# 04_ZYNQ_MISC_INTERFACE.net
KiCad netlist of a schematic drawn in Altium Designer
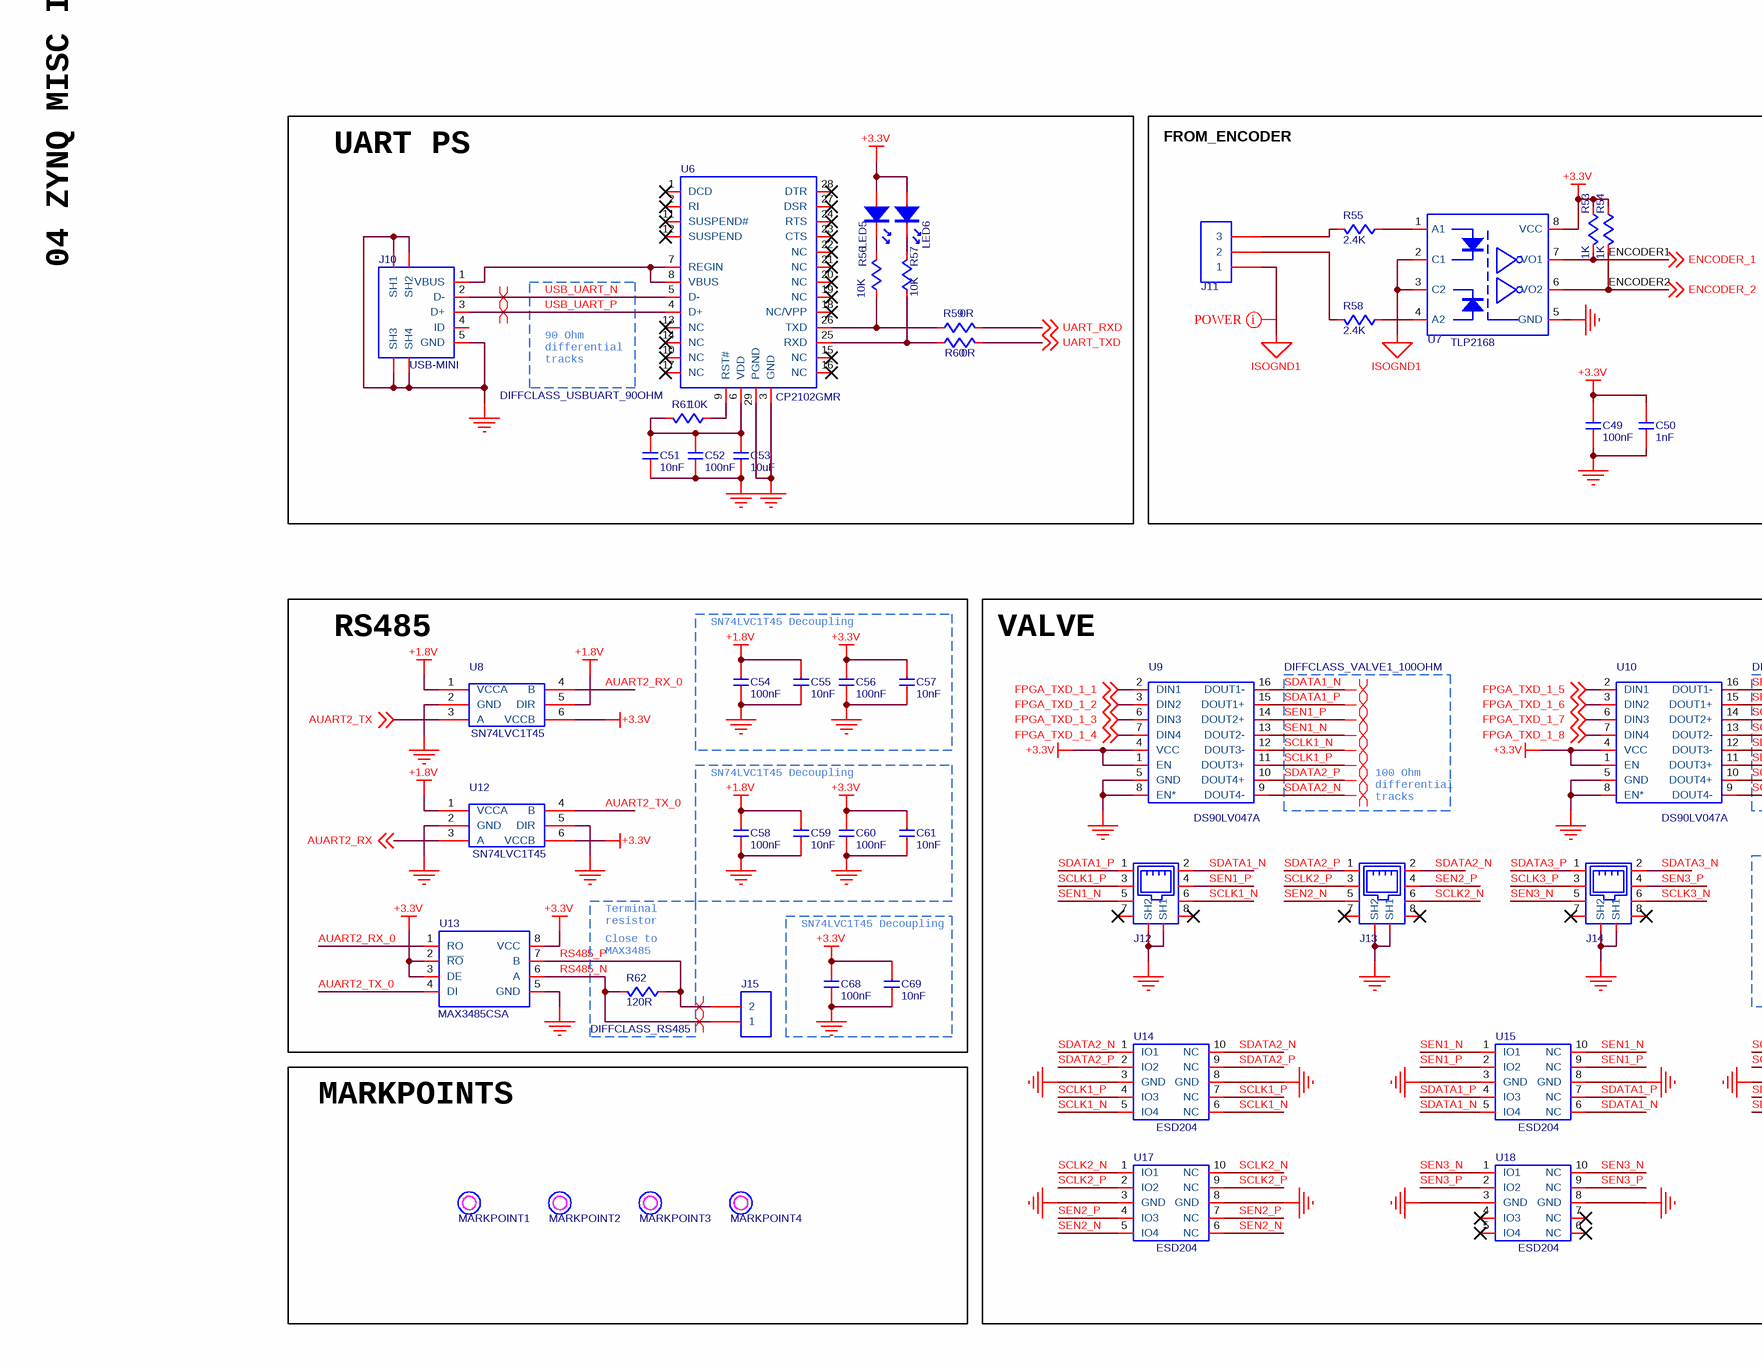
[diagram p0: 04_ZYNQ_MISC_INTERFACE.SchDoc, left]
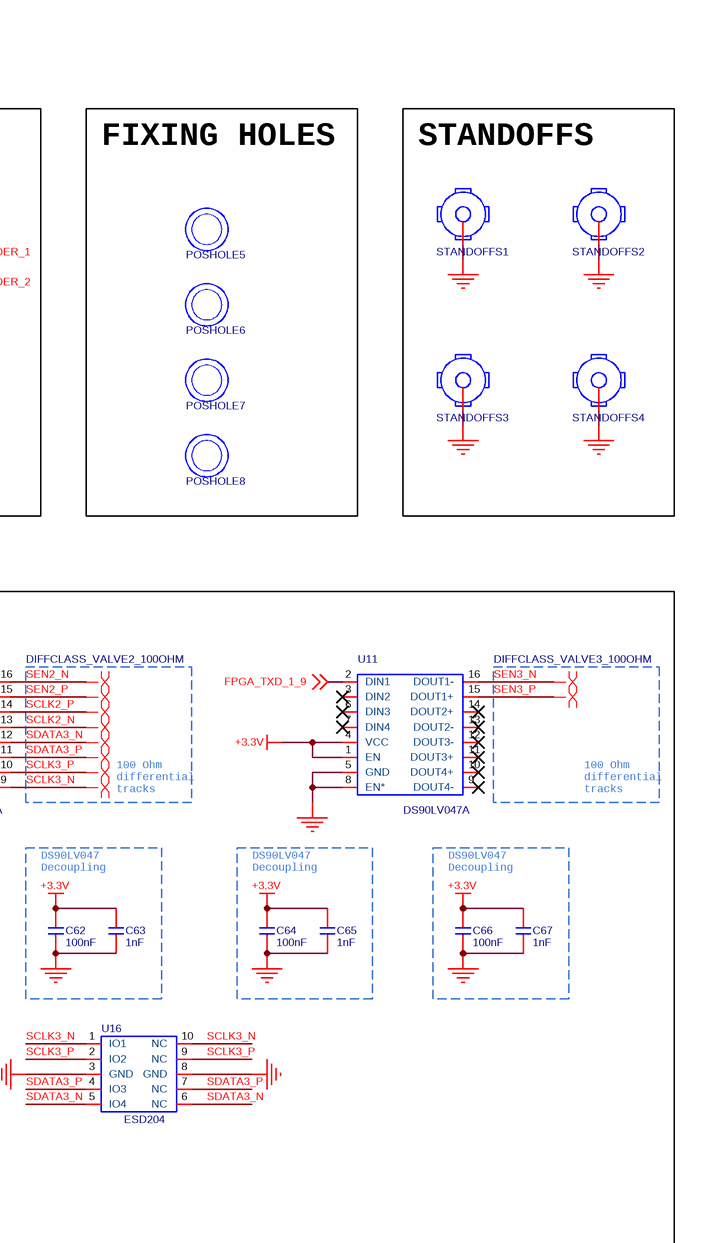
[diagram p1: 04_ZYNQ_MISC_INTERFACE.SchDoc, right]

(export (version "E")
  (design (tool "Eeschema 10.0.6"))
  (components
    (comp (ref "C49")
      (value "100nF")
      (footprint "zynq:C0402")
      (fields (field (name "VOLTAGE") "25V") (field (name "Comment") "C-NOMO"))
      (libsource (lib "mw") (part "C-NOMO"))
    )
    (comp (ref "C50")
      (value "1nF")
      (footprint "zynq:C0402")
      (fields (field (name "VOLTAGE") "25V") (field (name "Comment") "C-NOMO"))
      (libsource (lib "mw") (part "C-NOMO"))
    )
    (comp (ref "C51")
      (value "10nF")
      (footprint "zynq:C0402")
      (fields (field (name "VOLTAGE") "25V") (field (name "Comment") "C-NOMO"))
      (libsource (lib "zynq") (part "C-NOMO"))
    )
    (comp (ref "C52")
      (value "100nF")
      (footprint "zynq:C0402")
      (fields (field (name "VOLTAGE") "25V") (field (name "Comment") "C-NOMO"))
      (libsource (lib "zynq") (part "C-NOMO"))
    )
    (comp (ref "C53")
      (value "10uF")
      (footprint "zynq:C0805")
      (fields (field (name "VOLTAGE") "25V") (field (name "Comment") "C-NOMO"))
      (libsource (lib "zynq") (part "C-NOMO"))
    )
    (comp (ref "C54")
      (value "100nF")
      (footprint "zynq:C0402")
      (fields (field (name "VOLTAGE") "25V") (field (name "Comment") "C-NOMO"))
      (libsource (lib "zynq") (part "C-NOMO"))
    )
    (comp (ref "C55")
      (value "10nF")
      (footprint "zynq:C0402")
      (fields (field (name "VOLTAGE") "25V") (field (name "Comment") "C-NOMO"))
      (libsource (lib "zynq") (part "C-NOMO"))
    )
    (comp (ref "C56")
      (value "100nF")
      (footprint "zynq:C0402")
      (fields (field (name "VOLTAGE") "25V") (field (name "Comment") "C-NOMO"))
      (libsource (lib "zynq") (part "C-NOMO"))
    )
    (comp (ref "C57")
      (value "10nF")
      (footprint "zynq:C0402")
      (fields (field (name "VOLTAGE") "25V") (field (name "Comment") "C-NOMO"))
      (libsource (lib "zynq") (part "C-NOMO"))
    )
    (comp (ref "C58")
      (value "100nF")
      (footprint "zynq:C0402")
      (fields (field (name "VOLTAGE") "25V") (field (name "Comment") "C-NOMO"))
      (libsource (lib "zynq") (part "C-NOMO"))
    )
    (comp (ref "C59")
      (value "10nF")
      (footprint "zynq:C0402")
      (fields (field (name "VOLTAGE") "25V") (field (name "Comment") "C-NOMO"))
      (libsource (lib "zynq") (part "C-NOMO"))
    )
    (comp (ref "C60")
      (value "100nF")
      (footprint "zynq:C0402")
      (fields (field (name "VOLTAGE") "25V") (field (name "Comment") "C-NOMO"))
      (libsource (lib "zynq") (part "C-NOMO"))
    )
    (comp (ref "C61")
      (value "10nF")
      (footprint "zynq:C0402")
      (fields (field (name "VOLTAGE") "25V") (field (name "Comment") "C-NOMO"))
      (libsource (lib "zynq") (part "C-NOMO"))
    )
    (comp (ref "C62")
      (value "100nF")
      (footprint "zynq:C0402")
      (fields (field (name "VOLTAGE") "25V") (field (name "Comment") "C-NOMO"))
      (libsource (lib "zynq") (part "C-NOMO"))
    )
    (comp (ref "C63")
      (value "1nF")
      (footprint "zynq:C0402")
      (fields (field (name "VOLTAGE") "25V") (field (name "Comment") "C-NOMO"))
      (libsource (lib "zynq") (part "C-NOMO"))
    )
    (comp (ref "C64")
      (value "100nF")
      (footprint "zynq:C0402")
      (fields (field (name "VOLTAGE") "25V") (field (name "Comment") "C-NOMO"))
      (libsource (lib "zynq") (part "C-NOMO"))
    )
    (comp (ref "C65")
      (value "1nF")
      (footprint "zynq:C0402")
      (fields (field (name "VOLTAGE") "25V") (field (name "Comment") "C-NOMO"))
      (libsource (lib "zynq") (part "C-NOMO"))
    )
    (comp (ref "C66")
      (value "100nF")
      (footprint "zynq:C0402")
      (fields (field (name "VOLTAGE") "25V") (field (name "Comment") "C-NOMO"))
      (libsource (lib "zynq") (part "C-NOMO"))
    )
    (comp (ref "C67")
      (value "1nF")
      (footprint "zynq:C0402")
      (fields (field (name "VOLTAGE") "25V") (field (name "Comment") "C-NOMO"))
      (libsource (lib "zynq") (part "C-NOMO"))
    )
    (comp (ref "C68")
      (value "100nF")
      (footprint "zynq:C0402")
      (fields (field (name "VOLTAGE") "25V") (field (name "Comment") "C-NOMO"))
      (libsource (lib "zynq") (part "C-NOMO"))
    )
    (comp (ref "C69")
      (value "10nF")
      (footprint "zynq:C0402")
      (fields (field (name "VOLTAGE") "25V") (field (name "Comment") "C-NOMO"))
      (libsource (lib "zynq") (part "C-NOMO"))
    )
    (comp (ref "J10")
      (value "USB-MINI")
      (footprint "zynq:USB-MINI")
      (libsource (lib "zynq") (part "USB-MINI"))
    )
    (comp (ref "J11") (value "HDR1X3") (footprint "zynq:KF301-5.0-3P") (libsource (lib "mw") (part "HDR1X3")))
    (comp (ref "J12") (value "RJ45-UP") (footprint "zynq:RJ45-UP") (libsource (lib "mw") (part "RJ45-UP")))
    (comp (ref "J13") (value "RJ45-UP") (footprint "zynq:RJ45-UP") (libsource (lib "mw") (part "RJ45-UP")))
    (comp (ref "J14") (value "RJ45-UP") (footprint "zynq:RJ45-UP") (libsource (lib "mw") (part "RJ45-UP")))
    (comp (ref "J15")
      (value "HDR1X2")
      (footprint "zynq:KF301-5.0-2P")
      (libsource (lib "zynq") (part "HDR1X2"))
    )
    (comp (ref "LED5") (value "LED") (footprint "zynq:LED0603") (libsource (lib "zynq") (part "LED")))
    (comp (ref "LED6") (value "LED") (footprint "zynq:LED0603") (libsource (lib "zynq") (part "LED")))
    (comp (ref "MARKPOINT1")
      (value "MARKPOINT")
      (footprint "zynq:MARKPOINT-1.0")
      (libsource (lib "zynq") (part "MARKPOINT"))
    )
    (comp (ref "MARKPOINT2")
      (value "MARKPOINT")
      (footprint "zynq:MARKPOINT-1.0")
      (libsource (lib "zynq") (part "MARKPOINT"))
    )
    (comp (ref "MARKPOINT3")
      (value "MARKPOINT")
      (footprint "zynq:MARKPOINT-1.0")
      (libsource (lib "zynq") (part "MARKPOINT"))
    )
    (comp (ref "MARKPOINT4")
      (value "MARKPOINT")
      (footprint "zynq:MARKPOINT-1.0")
      (libsource (lib "zynq") (part "MARKPOINT"))
    )
    (comp (ref "POSHOLE5")
      (value "POSHOLE")
      (footprint "zynq:POSHOLE-3.2")
      (libsource (lib "zynq") (part "POSHOLE"))
    )
    (comp (ref "POSHOLE6")
      (value "POSHOLE")
      (footprint "zynq:POSHOLE-3.2")
      (libsource (lib "zynq") (part "POSHOLE"))
    )
    (comp (ref "POSHOLE7")
      (value "POSHOLE")
      (footprint "zynq:POSHOLE-3.2")
      (libsource (lib "zynq") (part "POSHOLE"))
    )
    (comp (ref "POSHOLE8")
      (value "POSHOLE")
      (footprint "zynq:POSHOLE-3.2")
      (libsource (lib "zynq") (part "POSHOLE"))
    )
    (comp (ref "R53")
      (value "1K")
      (footprint "zynq:R0402")
      (fields (field (name "Comment") "R"))
      (libsource (lib "mw") (part "R"))
    )
    (comp (ref "R54")
      (value "1K")
      (footprint "zynq:R0402")
      (fields (field (name "Comment") "R"))
      (libsource (lib "mw") (part "R"))
    )
    (comp (ref "R55")
      (value "2.4K")
      (footprint "zynq:R2512")
      (fields (field (name "Comment") "R"))
      (libsource (lib "mw") (part "R"))
    )
    (comp (ref "R56")
      (value "10K")
      (footprint "zynq:R0402")
      (fields (field (name "Comment") "R"))
      (libsource (lib "zynq") (part "R"))
    )
    (comp (ref "R57")
      (value "10K")
      (footprint "zynq:R0402")
      (fields (field (name "Comment") "R"))
      (libsource (lib "zynq") (part "R"))
    )
    (comp (ref "R58")
      (value "2.4K")
      (footprint "zynq:R2512")
      (fields (field (name "Comment") "R"))
      (libsource (lib "mw") (part "R"))
    )
    (comp (ref "R59")
      (value "0R")
      (footprint "zynq:R0402")
      (fields (field (name "Comment") "R"))
      (libsource (lib "zynq") (part "R"))
    )
    (comp (ref "R60")
      (value "0R")
      (footprint "zynq:R0402")
      (fields (field (name "Comment") "R"))
      (libsource (lib "zynq") (part "R"))
    )
    (comp (ref "R61")
      (value "10K")
      (footprint "zynq:R0402")
      (fields (field (name "Comment") "R"))
      (libsource (lib "zynq") (part "R"))
    )
    (comp (ref "R62")
      (value "120R")
      (footprint "zynq:R0402")
      (fields (field (name "Comment") "R"))
      (libsource (lib "zynq") (part "R"))
    )
    (comp (ref "STANDOFFS1")
      (value "STANDOFFS")
      (footprint "zynq:STANDOFFS-5-2.5")
      (libsource (lib "zynq") (part "STANDOFFS"))
    )
    (comp (ref "STANDOFFS2")
      (value "STANDOFFS")
      (footprint "zynq:STANDOFFS-5-2.5")
      (libsource (lib "zynq") (part "STANDOFFS"))
    )
    (comp (ref "STANDOFFS3")
      (value "STANDOFFS")
      (footprint "zynq:STANDOFFS-5-2.5")
      (libsource (lib "zynq") (part "STANDOFFS"))
    )
    (comp (ref "STANDOFFS4")
      (value "STANDOFFS")
      (footprint "zynq:STANDOFFS-5-2.5")
      (libsource (lib "zynq") (part "STANDOFFS"))
    )
    (comp (ref "U6")
      (value "CP2102GMR")
      (footprint "zynq:CP2102GMR")
      (libsource (lib "zynq") (part "CP2102GMR"))
    )
    (comp (ref "U7") (value "TLP2168") (footprint "TLP2168") (libsource (lib "mw") (part "TLP2168")))
    (comp (ref "U8")
      (value "SN74LVC1T45")
      (footprint "zynq:SN74LVC1T45")
      (libsource (lib "zynq") (part "SN74LVC1T45"))
    )
    (comp (ref "U9")
      (value "DS90LV047A")
      (footprint "zynq:DS90LV047")
      (libsource (lib "zynq") (part "DS90LV047A"))
    )
    (comp (ref "U10")
      (value "DS90LV047A")
      (footprint "zynq:DS90LV047")
      (libsource (lib "zynq") (part "DS90LV047A"))
    )
    (comp (ref "U11")
      (value "DS90LV047A")
      (footprint "zynq:DS90LV047")
      (libsource (lib "zynq") (part "DS90LV047A"))
    )
    (comp (ref "U12")
      (value "SN74LVC1T45")
      (footprint "zynq:SN74LVC1T45")
      (libsource (lib "zynq") (part "SN74LVC1T45"))
    )
    (comp (ref "U13")
      (value "MAX3485CSA")
      (footprint "zynq:MAX3485CSA")
      (libsource (lib "zynq") (part "MAX3485CSA"))
    )
    (comp (ref "U14") (value "ESD204") (footprint "zynq:ESD204") (libsource (lib "mw") (part "ESD204")))
    (comp (ref "U15") (value "ESD204") (footprint "zynq:ESD204") (libsource (lib "mw") (part "ESD204")))
    (comp (ref "U16") (value "ESD204") (footprint "zynq:ESD204") (libsource (lib "mw") (part "ESD204")))
    (comp (ref "U17") (value "ESD204") (footprint "zynq:ESD204") (libsource (lib "mw") (part "ESD204")))
    (comp (ref "U18") (value "ESD204") (footprint "zynq:ESD204") (libsource (lib "mw") (part "ESD204")))
  )
  (nets
    (net (code "1") (name "+1.8V") (class "Default")
      (node (ref "C54") (pin "1") (pinfunction "1_1") (pintype "passive"))
      (node (ref "C55") (pin "2") (pinfunction "2_2") (pintype "passive"))
      (node (ref "C58") (pin "1") (pinfunction "1_1") (pintype "passive"))
      (node (ref "C59") (pin "2") (pinfunction "2_2") (pintype "passive"))
      (node (ref "U12") (pin "1") (pinfunction "VCCA_1") (pintype "passive"))
      (node (ref "U8") (pin "1") (pinfunction "VCCA_1") (pintype "passive"))
      (node (ref "U8") (pin "5") (pinfunction "DIR_5") (pintype "passive"))
    )
    (net (code "2") (name "+3.3V") (class "Default")
      (node (ref "C49") (pin "2") (pinfunction "2_2") (pintype "passive"))
      (node (ref "C50") (pin "2") (pinfunction "2_2") (pintype "passive"))
      (node (ref "C56") (pin "1") (pinfunction "1_1") (pintype "passive"))
      (node (ref "C57") (pin "2") (pinfunction "2_2") (pintype "passive"))
      (node (ref "C60") (pin "1") (pinfunction "1_1") (pintype "passive"))
      (node (ref "C61") (pin "2") (pinfunction "2_2") (pintype "passive"))
      (node (ref "C62") (pin "1") (pinfunction "1_1") (pintype "passive"))
      (node (ref "C63") (pin "2") (pinfunction "2_2") (pintype "passive"))
      (node (ref "C64") (pin "1") (pinfunction "1_1") (pintype "passive"))
      (node (ref "C65") (pin "2") (pinfunction "2_2") (pintype "passive"))
      (node (ref "C66") (pin "1") (pinfunction "1_1") (pintype "passive"))
      (node (ref "C67") (pin "2") (pinfunction "2_2") (pintype "passive"))
      (node (ref "C68") (pin "1") (pinfunction "1_1") (pintype "passive"))
      (node (ref "C69") (pin "2") (pinfunction "2_2") (pintype "passive"))
      (node (ref "LED5") (pin "2") (pinfunction "2_2") (pintype "passive"))
      (node (ref "LED6") (pin "2") (pinfunction "2_2") (pintype "passive"))
      (node (ref "R53") (pin "2") (pinfunction "2_2") (pintype "passive"))
      (node (ref "R54") (pin "2") (pinfunction "2_2") (pintype "passive"))
      (node (ref "U10") (pin "1") (pinfunction "EN_1") (pintype "passive"))
      (node (ref "U10") (pin "4") (pinfunction "VCC_4") (pintype "passive"))
      (node (ref "U11") (pin "1") (pinfunction "EN_1") (pintype "passive"))
      (node (ref "U11") (pin "4") (pinfunction "VCC_4") (pintype "passive"))
      (node (ref "U12") (pin "6") (pinfunction "VCCB_6") (pintype "passive"))
      (node (ref "U13") (pin "2") (pinfunction "~{RO}_2") (pintype "passive"))
      (node (ref "U13") (pin "3") (pinfunction "DE_3") (pintype "passive"))
      (node (ref "U13") (pin "8") (pinfunction "VCC_8") (pintype "passive"))
      (node (ref "U7") (pin "8") (pinfunction "VCC_8") (pintype "passive"))
      (node (ref "U8") (pin "6") (pinfunction "VCCB_6") (pintype "passive"))
      (node (ref "U9") (pin "1") (pinfunction "EN_1") (pintype "passive"))
      (node (ref "U9") (pin "4") (pinfunction "VCC_4") (pintype "passive"))
    )
    (net (code "3") (name "/AUART2_RX_0") (class "Default")
      (node (ref "U13") (pin "1") (pinfunction "RO_1") (pintype "passive"))
      (node (ref "U8") (pin "4") (pinfunction "B_4") (pintype "passive"))
    )
    (net (code "4") (name "/AUART2_TX_0") (class "Default")
      (node (ref "U12") (pin "4") (pinfunction "B_4") (pintype "passive"))
      (node (ref "U13") (pin "4") (pinfunction "DI_4") (pintype "passive"))
    )
    (net (code "5") (name "/RS485_N") (class "Default")
      (node (ref "J15") (pin "1") (pinfunction "1_1") (pintype "passive"))
      (node (ref "R62") (pin "1") (pinfunction "1_1") (pintype "passive"))
      (node (ref "U13") (pin "6") (pinfunction "A_6") (pintype "passive"))
    )
    (net (code "6") (name "/RS485_P") (class "Default")
      (node (ref "J15") (pin "2") (pinfunction "2_2") (pintype "passive"))
      (node (ref "R62") (pin "2") (pinfunction "2_2") (pintype "passive"))
      (node (ref "U13") (pin "7") (pinfunction "B_7") (pintype "passive"))
    )
    (net (code "7") (name "/SCLK1_N") (class "Default")
      (node (ref "J12") (pin "6") (pinfunction "6_6") (pintype "passive"))
      (node (ref "U14") (pin "5") (pinfunction "IO4_5") (pintype "passive"))
      (node (ref "U14") (pin "6") (pinfunction "NC_6") (pintype "passive"))
      (node (ref "U9") (pin "12") (pinfunction "DOUT3-_12") (pintype "passive"))
    )
    (net (code "8") (name "/SCLK1_P") (class "Default")
      (node (ref "J12") (pin "3") (pinfunction "3_3") (pintype "passive"))
      (node (ref "U14") (pin "4") (pinfunction "IO3_4") (pintype "passive"))
      (node (ref "U14") (pin "7") (pinfunction "NC_7") (pintype "passive"))
      (node (ref "U9") (pin "11") (pinfunction "DOUT3+_11") (pintype "passive"))
    )
    (net (code "9") (name "/SCLK2_N") (class "Default")
      (node (ref "J13") (pin "6") (pinfunction "6_6") (pintype "passive"))
      (node (ref "U10") (pin "13") (pinfunction "DOUT2-_13") (pintype "passive"))
      (node (ref "U17") (pin "1") (pinfunction "IO1_1") (pintype "passive"))
      (node (ref "U17") (pin "10") (pinfunction "NC_10") (pintype "passive"))
    )
    (net (code "10") (name "/SCLK2_P") (class "Default")
      (node (ref "J13") (pin "3") (pinfunction "3_3") (pintype "passive"))
      (node (ref "U10") (pin "14") (pinfunction "DOUT2+_14") (pintype "passive"))
      (node (ref "U17") (pin "2") (pinfunction "IO2_2") (pintype "passive"))
      (node (ref "U17") (pin "9") (pinfunction "NC_9") (pintype "passive"))
    )
    (net (code "11") (name "/SCLK3_N") (class "Default")
      (node (ref "J14") (pin "6") (pinfunction "6_6") (pintype "passive"))
      (node (ref "U10") (pin "9") (pinfunction "DOUT4-_9") (pintype "passive"))
      (node (ref "U16") (pin "1") (pinfunction "IO1_1") (pintype "passive"))
      (node (ref "U16") (pin "10") (pinfunction "NC_10") (pintype "passive"))
    )
    (net (code "12") (name "/SCLK3_P") (class "Default")
      (node (ref "J14") (pin "3") (pinfunction "3_3") (pintype "passive"))
      (node (ref "U10") (pin "10") (pinfunction "DOUT4+_10") (pintype "passive"))
      (node (ref "U16") (pin "2") (pinfunction "IO2_2") (pintype "passive"))
      (node (ref "U16") (pin "9") (pinfunction "NC_9") (pintype "passive"))
    )
    (net (code "13") (name "/SDATA1_N") (class "Default")
      (node (ref "J12") (pin "2") (pinfunction "2_2") (pintype "passive"))
      (node (ref "U15") (pin "5") (pinfunction "IO4_5") (pintype "passive"))
      (node (ref "U15") (pin "6") (pinfunction "NC_6") (pintype "passive"))
      (node (ref "U9") (pin "16") (pinfunction "DOUT1-_16") (pintype "passive"))
    )
    (net (code "14") (name "/SDATA1_P") (class "Default")
      (node (ref "J12") (pin "1") (pinfunction "1_1") (pintype "passive"))
      (node (ref "U15") (pin "4") (pinfunction "IO3_4") (pintype "passive"))
      (node (ref "U15") (pin "7") (pinfunction "NC_7") (pintype "passive"))
      (node (ref "U9") (pin "15") (pinfunction "DOUT1+_15") (pintype "passive"))
    )
    (net (code "15") (name "/SDATA2_N") (class "Default")
      (node (ref "J13") (pin "2") (pinfunction "2_2") (pintype "passive"))
      (node (ref "U14") (pin "1") (pinfunction "IO1_1") (pintype "passive"))
      (node (ref "U14") (pin "10") (pinfunction "NC_10") (pintype "passive"))
      (node (ref "U9") (pin "9") (pinfunction "DOUT4-_9") (pintype "passive"))
    )
    (net (code "16") (name "/SDATA2_P") (class "Default")
      (node (ref "J13") (pin "1") (pinfunction "1_1") (pintype "passive"))
      (node (ref "U14") (pin "2") (pinfunction "IO2_2") (pintype "passive"))
      (node (ref "U14") (pin "9") (pinfunction "NC_9") (pintype "passive"))
      (node (ref "U9") (pin "10") (pinfunction "DOUT4+_10") (pintype "passive"))
    )
    (net (code "17") (name "/SDATA3_N") (class "Default")
      (node (ref "J14") (pin "2") (pinfunction "2_2") (pintype "passive"))
      (node (ref "U10") (pin "12") (pinfunction "DOUT3-_12") (pintype "passive"))
      (node (ref "U16") (pin "5") (pinfunction "IO4_5") (pintype "passive"))
      (node (ref "U16") (pin "6") (pinfunction "NC_6") (pintype "passive"))
    )
    (net (code "18") (name "/SDATA3_P") (class "Default")
      (node (ref "J14") (pin "1") (pinfunction "1_1") (pintype "passive"))
      (node (ref "U10") (pin "11") (pinfunction "DOUT3+_11") (pintype "passive"))
      (node (ref "U16") (pin "4") (pinfunction "IO3_4") (pintype "passive"))
      (node (ref "U16") (pin "7") (pinfunction "NC_7") (pintype "passive"))
    )
    (net (code "19") (name "/SEN1_N") (class "Default")
      (node (ref "J12") (pin "5") (pinfunction "5_5") (pintype "passive"))
      (node (ref "U15") (pin "1") (pinfunction "IO1_1") (pintype "passive"))
      (node (ref "U15") (pin "10") (pinfunction "NC_10") (pintype "passive"))
      (node (ref "U9") (pin "13") (pinfunction "DOUT2-_13") (pintype "passive"))
    )
    (net (code "20") (name "/SEN1_P") (class "Default")
      (node (ref "J12") (pin "4") (pinfunction "4_4") (pintype "passive"))
      (node (ref "U15") (pin "2") (pinfunction "IO2_2") (pintype "passive"))
      (node (ref "U15") (pin "9") (pinfunction "NC_9") (pintype "passive"))
      (node (ref "U9") (pin "14") (pinfunction "DOUT2+_14") (pintype "passive"))
    )
    (net (code "21") (name "/SEN2_N") (class "Default")
      (node (ref "J13") (pin "5") (pinfunction "5_5") (pintype "passive"))
      (node (ref "U10") (pin "16") (pinfunction "DOUT1-_16") (pintype "passive"))
      (node (ref "U17") (pin "5") (pinfunction "IO4_5") (pintype "passive"))
      (node (ref "U17") (pin "6") (pinfunction "NC_6") (pintype "passive"))
    )
    (net (code "22") (name "/SEN2_P") (class "Default")
      (node (ref "J13") (pin "4") (pinfunction "4_4") (pintype "passive"))
      (node (ref "U10") (pin "15") (pinfunction "DOUT1+_15") (pintype "passive"))
      (node (ref "U17") (pin "4") (pinfunction "IO3_4") (pintype "passive"))
      (node (ref "U17") (pin "7") (pinfunction "NC_7") (pintype "passive"))
    )
    (net (code "23") (name "/SEN3_N") (class "Default")
      (node (ref "J14") (pin "5") (pinfunction "5_5") (pintype "passive"))
      (node (ref "U11") (pin "16") (pinfunction "DOUT1-_16") (pintype "passive"))
      (node (ref "U18") (pin "1") (pinfunction "IO1_1") (pintype "passive"))
      (node (ref "U18") (pin "10") (pinfunction "NC_10") (pintype "passive"))
    )
    (net (code "24") (name "/SEN3_P") (class "Default")
      (node (ref "J14") (pin "4") (pinfunction "4_4") (pintype "passive"))
      (node (ref "U11") (pin "15") (pinfunction "DOUT1+_15") (pintype "passive"))
      (node (ref "U18") (pin "2") (pinfunction "IO2_2") (pintype "passive"))
      (node (ref "U18") (pin "9") (pinfunction "NC_9") (pintype "passive"))
    )
    (net (code "25") (name "/USB_UART_N") (class "Default")
      (node (ref "J10") (pin "2") (pinfunction "D-_2") (pintype "passive"))
      (node (ref "U6") (pin "5") (pinfunction "D-_5") (pintype "passive"))
    )
    (net (code "26") (name "/USB_UART_P") (class "Default")
      (node (ref "J10") (pin "3") (pinfunction "D+_3") (pintype "passive"))
      (node (ref "U6") (pin "4") (pinfunction "D+_4") (pintype "passive"))
    )
    (net (code "27") (name "AUART2_RX") (class "Default")
      (node (ref "U12") (pin "3") (pinfunction "A_3") (pintype "passive"))
    )
    (net (code "28") (name "AUART2_TX") (class "Default")
      (node (ref "U8") (pin "3") (pinfunction "A_3") (pintype "passive"))
    )
    (net (code "29") (name "ENCODER_1") (class "Default")
      (node (ref "R53") (pin "1") (pinfunction "1_1") (pintype "passive"))
      (node (ref "U7") (pin "7") (pinfunction "VO1_7") (pintype "passive"))
    )
    (net (code "30") (name "ENCODER_2") (class "Default")
      (node (ref "R54") (pin "1") (pinfunction "1_1") (pintype "passive"))
      (node (ref "U7") (pin "6") (pinfunction "VO2_6") (pintype "passive"))
    )
    (net (code "31") (name "FPGA_TXD_1_1") (class "Default")
      (node (ref "U9") (pin "2") (pinfunction "DIN1_2") (pintype "passive"))
    )
    (net (code "32") (name "FPGA_TXD_1_2") (class "Default")
      (node (ref "U9") (pin "3") (pinfunction "DIN2_3") (pintype "passive"))
    )
    (net (code "33") (name "FPGA_TXD_1_3") (class "Default")
      (node (ref "U9") (pin "6") (pinfunction "DIN3_6") (pintype "passive"))
    )
    (net (code "34") (name "FPGA_TXD_1_4") (class "Default")
      (node (ref "U9") (pin "7") (pinfunction "DIN4_7") (pintype "passive"))
    )
    (net (code "35") (name "FPGA_TXD_1_5") (class "Default")
      (node (ref "U10") (pin "2") (pinfunction "DIN1_2") (pintype "passive"))
    )
    (net (code "36") (name "FPGA_TXD_1_6") (class "Default")
      (node (ref "U10") (pin "3") (pinfunction "DIN2_3") (pintype "passive"))
    )
    (net (code "37") (name "FPGA_TXD_1_7") (class "Default")
      (node (ref "U10") (pin "6") (pinfunction "DIN3_6") (pintype "passive"))
    )
    (net (code "38") (name "FPGA_TXD_1_8") (class "Default")
      (node (ref "U10") (pin "7") (pinfunction "DIN4_7") (pintype "passive"))
    )
    (net (code "39") (name "FPGA_TXD_1_9") (class "Default")
      (node (ref "U11") (pin "2") (pinfunction "DIN1_2") (pintype "passive"))
    )
    (net (code "40") (name "GND") (class "Default")
      (node (ref "C49") (pin "1") (pinfunction "1_1") (pintype "passive"))
      (node (ref "C50") (pin "1") (pinfunction "1_1") (pintype "passive"))
      (node (ref "C51") (pin "1") (pinfunction "1_1") (pintype "passive"))
      (node (ref "C52") (pin "1") (pinfunction "1_1") (pintype "passive"))
      (node (ref "C53") (pin "2") (pinfunction "2_2") (pintype "passive"))
      (node (ref "C54") (pin "2") (pinfunction "2_2") (pintype "passive"))
      (node (ref "C55") (pin "1") (pinfunction "1_1") (pintype "passive"))
      (node (ref "C56") (pin "2") (pinfunction "2_2") (pintype "passive"))
      (node (ref "C57") (pin "1") (pinfunction "1_1") (pintype "passive"))
      (node (ref "C58") (pin "2") (pinfunction "2_2") (pintype "passive"))
      (node (ref "C59") (pin "1") (pinfunction "1_1") (pintype "passive"))
      (node (ref "C60") (pin "2") (pinfunction "2_2") (pintype "passive"))
      (node (ref "C61") (pin "1") (pinfunction "1_1") (pintype "passive"))
      (node (ref "C62") (pin "2") (pinfunction "2_2") (pintype "passive"))
      (node (ref "C63") (pin "1") (pinfunction "1_1") (pintype "passive"))
      (node (ref "C64") (pin "2") (pinfunction "2_2") (pintype "passive"))
      (node (ref "C65") (pin "1") (pinfunction "1_1") (pintype "passive"))
      (node (ref "C66") (pin "2") (pinfunction "2_2") (pintype "passive"))
      (node (ref "C67") (pin "1") (pinfunction "1_1") (pintype "passive"))
      (node (ref "C68") (pin "2") (pinfunction "2_2") (pintype "passive"))
      (node (ref "C69") (pin "1") (pinfunction "1_1") (pintype "passive"))
      (node (ref "J10") (pin "5") (pinfunction "GND_5") (pintype "passive"))
      (node (ref "J10") (pin "SH1") (pinfunction "SH1_SH1") (pintype "passive"))
      (node (ref "J10") (pin "SH2") (pinfunction "SH2_SH2") (pintype "passive"))
      (node (ref "J10") (pin "SH3") (pinfunction "SH3_SH3") (pintype "passive"))
      (node (ref "J10") (pin "SH4") (pinfunction "SH4_SH4") (pintype "passive"))
      (node (ref "J12") (pin "SH1") (pinfunction "SH1_SH1") (pintype "passive"))
      (node (ref "J12") (pin "SH2") (pinfunction "SH2_SH2") (pintype "passive"))
      (node (ref "J13") (pin "SH1") (pinfunction "SH1_SH1") (pintype "passive"))
      (node (ref "J13") (pin "SH2") (pinfunction "SH2_SH2") (pintype "passive"))
      (node (ref "J14") (pin "SH1") (pinfunction "SH1_SH1") (pintype "passive"))
      (node (ref "J14") (pin "SH2") (pinfunction "SH2_SH2") (pintype "passive"))
      (node (ref "STANDOFFS1") (pin "0") (pintype "passive"))
      (node (ref "STANDOFFS2") (pin "0") (pintype "passive"))
      (node (ref "STANDOFFS3") (pin "0") (pintype "passive"))
      (node (ref "STANDOFFS4") (pin "0") (pintype "passive"))
      (node (ref "U10") (pin "5") (pinfunction "GND_5") (pintype "passive"))
      (node (ref "U10") (pin "8") (pinfunction "EN*_8") (pintype "passive"))
      (node (ref "U11") (pin "5") (pinfunction "GND_5") (pintype "passive"))
      (node (ref "U11") (pin "8") (pinfunction "EN*_8") (pintype "passive"))
      (node (ref "U12") (pin "2") (pinfunction "GND_2") (pintype "passive"))
      (node (ref "U12") (pin "5") (pinfunction "DIR_5") (pintype "passive"))
      (node (ref "U13") (pin "5") (pinfunction "GND_5") (pintype "passive"))
      (node (ref "U14") (pin "3") (pinfunction "GND_3") (pintype "passive"))
      (node (ref "U14") (pin "8") (pinfunction "GND_8") (pintype "passive"))
      (node (ref "U15") (pin "3") (pinfunction "GND_3") (pintype "passive"))
      (node (ref "U15") (pin "8") (pinfunction "GND_8") (pintype "passive"))
      (node (ref "U16") (pin "3") (pinfunction "GND_3") (pintype "passive"))
      (node (ref "U16") (pin "8") (pinfunction "GND_8") (pintype "passive"))
      (node (ref "U17") (pin "3") (pinfunction "GND_3") (pintype "passive"))
      (node (ref "U17") (pin "8") (pinfunction "GND_8") (pintype "passive"))
      (node (ref "U18") (pin "3") (pinfunction "GND_3") (pintype "passive"))
      (node (ref "U18") (pin "8") (pinfunction "GND_8") (pintype "passive"))
      (node (ref "U6") (pin "29") (pinfunction "PGND_29") (pintype "passive"))
      (node (ref "U6") (pin "3") (pinfunction "GND_3") (pintype "passive"))
      (node (ref "U7") (pin "5") (pinfunction "GND_5") (pintype "passive"))
      (node (ref "U8") (pin "2") (pinfunction "GND_2") (pintype "passive"))
      (node (ref "U9") (pin "5") (pinfunction "GND_5") (pintype "passive"))
      (node (ref "U9") (pin "8") (pinfunction "EN*_8") (pintype "passive"))
    )
    (net (code "41") (name "ISOGND1") (class "Default")
      (node (ref "J11") (pin "1") (pinfunction "1_1") (pintype "passive"))
      (node (ref "U7") (pin "2") (pinfunction "C1_2") (pintype "passive"))
      (node (ref "U7") (pin "3") (pinfunction "C2_3") (pintype "passive"))
    )
    (net (code "42") (name "Net-(J10-VBUS)") (class "Default")
      (node (ref "J10") (pin "1") (pinfunction "VBUS_1") (pintype "passive"))
      (node (ref "U6") (pin "7") (pinfunction "REGIN_7") (pintype "passive"))
      (node (ref "U6") (pin "8") (pinfunction "VBUS_8") (pintype "passive"))
    )
    (net (code "43") (name "Net-(J11-Pad2)") (class "Default")
      (node (ref "J11") (pin "2") (pinfunction "2_2") (pintype "passive"))
      (node (ref "R58") (pin "1") (pinfunction "1_1") (pintype "passive"))
    )
    (net (code "44") (name "Net-(J11-Pad3)") (class "Default")
      (node (ref "J11") (pin "3") (pinfunction "3_3") (pintype "passive"))
      (node (ref "R55") (pin "1") (pinfunction "1_1") (pintype "passive"))
    )
    (net (code "45") (name "Net-(LED5-Pad1)") (class "Default")
      (node (ref "LED5") (pin "1") (pinfunction "1_1") (pintype "passive"))
      (node (ref "R56") (pin "1") (pinfunction "1_1") (pintype "passive"))
    )
    (net (code "46") (name "Net-(LED6-Pad1)") (class "Default")
      (node (ref "LED6") (pin "1") (pinfunction "1_1") (pintype "passive"))
      (node (ref "R57") (pin "1") (pinfunction "1_1") (pintype "passive"))
    )
    (net (code "47") (name "Net-(U6-RST#)") (class "Default")
      (node (ref "R61") (pin "2") (pinfunction "2_2") (pintype "passive"))
      (node (ref "U6") (pin "9") (pinfunction "RST#_9") (pintype "passive"))
    )
    (net (code "48") (name "Net-(U6-RXD)") (class "Default")
      (node (ref "R57") (pin "2") (pinfunction "2_2") (pintype "passive"))
      (node (ref "R60") (pin "2") (pinfunction "2_2") (pintype "passive"))
      (node (ref "U6") (pin "25") (pinfunction "RXD_25") (pintype "passive"))
    )
    (net (code "49") (name "Net-(U6-TXD)") (class "Default")
      (node (ref "R56") (pin "2") (pinfunction "2_2") (pintype "passive"))
      (node (ref "R59") (pin "2") (pinfunction "2_2") (pintype "passive"))
      (node (ref "U6") (pin "26") (pinfunction "TXD_26") (pintype "passive"))
    )
    (net (code "50") (name "Net-(U6-VDD)") (class "Default")
      (node (ref "C51") (pin "2") (pinfunction "2_2") (pintype "passive"))
      (node (ref "C52") (pin "2") (pinfunction "2_2") (pintype "passive"))
      (node (ref "C53") (pin "1") (pinfunction "1_1") (pintype "passive"))
      (node (ref "R61") (pin "1") (pinfunction "1_1") (pintype "passive"))
      (node (ref "U6") (pin "6") (pinfunction "VDD_6") (pintype "passive"))
    )
    (net (code "51") (name "Net-(U7-A1)") (class "Default")
      (node (ref "R55") (pin "2") (pinfunction "2_2") (pintype "passive"))
      (node (ref "U7") (pin "1") (pinfunction "A1_1") (pintype "passive"))
    )
    (net (code "52") (name "Net-(U7-A2)") (class "Default")
      (node (ref "R58") (pin "2") (pinfunction "2_2") (pintype "passive"))
      (node (ref "U7") (pin "4") (pinfunction "A2_4") (pintype "passive"))
    )
    (net (code "53") (name "UART_RXD") (class "Default")
      (node (ref "R59") (pin "1") (pinfunction "1_1") (pintype "passive"))
    )
    (net (code "54") (name "UART_TXD") (class "Default")
      (node (ref "R60") (pin "1") (pinfunction "1_1") (pintype "passive"))
    )
    (net (code "55") (name "unconnected-(J10-ID-Pad4)") (class "Default")
      (node (ref "J10") (pin "4") (pinfunction "ID_4") (pintype "passive"))
    )
    (net (code "56") (name "unconnected-(J12-Pad7)") (class "Default")
      (node (ref "J12") (pin "7") (pinfunction "7_7") (pintype "passive+no_connect"))
    )
    (net (code "57") (name "unconnected-(J12-Pad8)") (class "Default")
      (node (ref "J12") (pin "8") (pinfunction "8_8") (pintype "passive+no_connect"))
    )
    (net (code "58") (name "unconnected-(J13-Pad7)") (class "Default")
      (node (ref "J13") (pin "7") (pinfunction "7_7") (pintype "passive+no_connect"))
    )
    (net (code "59") (name "unconnected-(J13-Pad8)") (class "Default")
      (node (ref "J13") (pin "8") (pinfunction "8_8") (pintype "passive+no_connect"))
    )
    (net (code "60") (name "unconnected-(J14-Pad7)") (class "Default")
      (node (ref "J14") (pin "7") (pinfunction "7_7") (pintype "passive+no_connect"))
    )
    (net (code "61") (name "unconnected-(J14-Pad8)") (class "Default")
      (node (ref "J14") (pin "8") (pinfunction "8_8") (pintype "passive+no_connect"))
    )
    (net (code "62") (name "unconnected-(U6-CTS-Pad23)") (class "Default")
      (node (ref "U6") (pin "23") (pinfunction "CTS_23") (pintype "passive+no_connect"))
    )
    (net (code "63") (name "unconnected-(U6-DCD-Pad1)") (class "Default")
      (node (ref "U6") (pin "1") (pinfunction "DCD_1") (pintype "passive+no_connect"))
    )
    (net (code "64") (name "unconnected-(U6-DSR-Pad27)") (class "Default")
      (node (ref "U6") (pin "27") (pinfunction "DSR_27") (pintype "passive+no_connect"))
    )
    (net (code "65") (name "unconnected-(U6-DTR-Pad28)") (class "Default")
      (node (ref "U6") (pin "28") (pinfunction "DTR_28") (pintype "passive+no_connect"))
    )
    (net (code "66") (name "unconnected-(U6-NC-Pad10)") (class "Default")
      (node (ref "U6") (pin "10") (pinfunction "NC_10") (pintype "passive+no_connect"))
    )
    (net (code "67") (name "unconnected-(U6-NC-Pad13)") (class "Default")
      (node (ref "U6") (pin "13") (pinfunction "NC_13") (pintype "passive+no_connect"))
    )
    (net (code "68") (name "unconnected-(U6-NC-Pad14)") (class "Default")
      (node (ref "U6") (pin "14") (pinfunction "NC_14") (pintype "passive+no_connect"))
    )
    (net (code "69") (name "unconnected-(U6-NC-Pad15)") (class "Default")
      (node (ref "U6") (pin "15") (pinfunction "NC_15") (pintype "passive+no_connect"))
    )
    (net (code "70") (name "unconnected-(U6-NC-Pad16)") (class "Default")
      (node (ref "U6") (pin "16") (pinfunction "NC_16") (pintype "passive+no_connect"))
    )
    (net (code "71") (name "unconnected-(U6-NC-Pad17)") (class "Default")
      (node (ref "U6") (pin "17") (pinfunction "NC_17") (pintype "passive+no_connect"))
    )
    (net (code "72") (name "unconnected-(U6-NC-Pad19)") (class "Default")
      (node (ref "U6") (pin "19") (pinfunction "NC_19") (pintype "passive+no_connect"))
    )
    (net (code "73") (name "unconnected-(U6-NC-Pad20)") (class "Default")
      (node (ref "U6") (pin "20") (pinfunction "NC_20") (pintype "passive+no_connect"))
    )
    (net (code "74") (name "unconnected-(U6-NC-Pad21)") (class "Default")
      (node (ref "U6") (pin "21") (pinfunction "NC_21") (pintype "passive+no_connect"))
    )
    (net (code "75") (name "unconnected-(U6-NC-Pad22)") (class "Default")
      (node (ref "U6") (pin "22") (pinfunction "NC_22") (pintype "passive+no_connect"))
    )
    (net (code "76") (name "unconnected-(U6-NC{slash}VPP-Pad18)") (class "Default")
      (node (ref "U6") (pin "18") (pinfunction "NC/VPP_18") (pintype "passive+no_connect"))
    )
    (net (code "77") (name "unconnected-(U6-RI-Pad2)") (class "Default")
      (node (ref "U6") (pin "2") (pinfunction "RI_2") (pintype "passive+no_connect"))
    )
    (net (code "78") (name "unconnected-(U6-RTS-Pad24)") (class "Default")
      (node (ref "U6") (pin "24") (pinfunction "RTS_24") (pintype "passive+no_connect"))
    )
    (net (code "79") (name "unconnected-(U6-SUSPEND#-Pad11)") (class "Default")
      (node (ref "U6") (pin "11") (pinfunction "SUSPEND#_11") (pintype "passive+no_connect"))
    )
    (net (code "80") (name "unconnected-(U6-SUSPEND-Pad12)") (class "Default")
      (node (ref "U6") (pin "12") (pinfunction "SUSPEND_12") (pintype "passive+no_connect"))
    )
    (net (code "81") (name "unconnected-(U11-DIN2-Pad3)") (class "Default")
      (node (ref "U11") (pin "3") (pinfunction "DIN2_3") (pintype "passive+no_connect"))
    )
    (net (code "82") (name "unconnected-(U11-DIN3-Pad6)") (class "Default")
      (node (ref "U11") (pin "6") (pinfunction "DIN3_6") (pintype "passive+no_connect"))
    )
    (net (code "83") (name "unconnected-(U11-DIN4-Pad7)") (class "Default")
      (node (ref "U11") (pin "7") (pinfunction "DIN4_7") (pintype "passive+no_connect"))
    )
    (net (code "84") (name "unconnected-(U11-DOUT2+-Pad14)") (class "Default")
      (node (ref "U11") (pin "14") (pinfunction "DOUT2+_14") (pintype "passive+no_connect"))
    )
    (net (code "85") (name "unconnected-(U11-DOUT2--Pad13)") (class "Default")
      (node (ref "U11") (pin "13") (pinfunction "DOUT2-_13") (pintype "passive+no_connect"))
    )
    (net (code "86") (name "unconnected-(U11-DOUT3+-Pad11)") (class "Default")
      (node (ref "U11") (pin "11") (pinfunction "DOUT3+_11") (pintype "passive+no_connect"))
    )
    (net (code "87") (name "unconnected-(U11-DOUT3--Pad12)") (class "Default")
      (node (ref "U11") (pin "12") (pinfunction "DOUT3-_12") (pintype "passive+no_connect"))
    )
    (net (code "88") (name "unconnected-(U11-DOUT4+-Pad10)") (class "Default")
      (node (ref "U11") (pin "10") (pinfunction "DOUT4+_10") (pintype "passive+no_connect"))
    )
    (net (code "89") (name "unconnected-(U11-DOUT4--Pad9)") (class "Default")
      (node (ref "U11") (pin "9") (pinfunction "DOUT4-_9") (pintype "passive+no_connect"))
    )
    (net (code "90") (name "unconnected-(U18-IO3-Pad4)") (class "Default")
      (node (ref "U18") (pin "4") (pinfunction "IO3_4") (pintype "passive+no_connect"))
    )
    (net (code "91") (name "unconnected-(U18-IO4-Pad5)") (class "Default")
      (node (ref "U18") (pin "5") (pinfunction "IO4_5") (pintype "passive+no_connect"))
    )
    (net (code "92") (name "unconnected-(U18-NC-Pad6)") (class "Default")
      (node (ref "U18") (pin "6") (pinfunction "NC_6") (pintype "passive+no_connect"))
    )
    (net (code "93") (name "unconnected-(U18-NC-Pad7)") (class "Default")
      (node (ref "U18") (pin "7") (pinfunction "NC_7") (pintype "passive+no_connect"))
    )
  )
)
